# GPS_lure.net
KiCad netlist of a schematic drawn in EAGLE
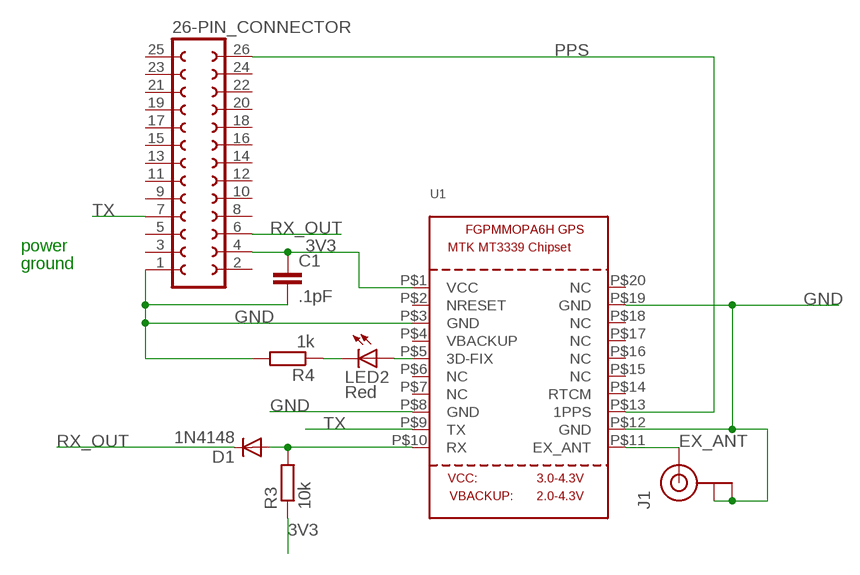
[diagram p0: schematic, sheet 1]

(export (version "E")
  (design (tool "Eeschema 10.0.6"))
  (components
    (comp (ref "26-PIN_CONNECTOR")
      (value "FE13-2W")
      (footprint "eagle-import:FE13-2W")
      (libsource (lib "eagle-import") (part "FE13-2W"))
    )
    (comp (ref "C1")
      (value ".1pF")
      (footprint "eagle-import:C0805")
      (libsource (lib "eagle-import") (part "C-EUC0805"))
    )
    (comp (ref "D1")
      (value "1N4148")
      (footprint "eagle-import:SOD123")
      (libsource (lib "eagle-import") (part "DIODE-SOD123"))
    )
    (comp (ref "J1")
      (value "U.FL")
      (footprint "eagle-import:U.FL")
      (libsource (lib "eagle-import") (part "U.FL"))
    )
    (comp (ref "LED2")
      (value "Red")
      (footprint "eagle-import:CHIPLED_1206")
      (libsource (lib "eagle-import") (part "LEDCHIPLED_1206"))
    )
    (comp (ref "R3")
      (value "10k")
      (footprint "eagle-import:M1206")
      (libsource (lib "eagle-import") (part "R-EU_M1206"))
    )
    (comp (ref "R4")
      (value "1k")
      (footprint "eagle-import:M1206")
      (libsource (lib "eagle-import") (part "R-EU_M1206"))
    )
    (comp (ref "U1")
      (value "GPS_FGPMMOPA6H")
      (footprint "eagle-import:FGPMMOPA6H")
      (libsource (lib "eagle-import") (part "GPS_FGPMMOPA6H"))
    )
  )
  (nets
    (net (code "1") (name "/3V3") (class "Default")
      (node (ref "26-PIN_CONNECTOR") (pin "4") (pinfunction "4_4") (pintype "passive"))
      (node (ref "C1") (pin "1") (pinfunction "1_1") (pintype "passive"))
      (node (ref "R3") (pin "1") (pinfunction "1_1") (pintype "passive"))
      (node (ref "U1") (pin "P$1") (pinfunction "VCC_P$1") (pintype "bidirectional"))
    )
    (net (code "2") (name "/EX_ANT") (class "Default")
      (node (ref "J1") (pin "P$3") (pinfunction "SIGNAL_P$3") (pintype "bidirectional"))
      (node (ref "U1") (pin "P$11") (pinfunction "EX_ANT_P$11") (pintype "bidirectional"))
    )
    (net (code "3") (name "/GND") (class "Default")
      (node (ref "26-PIN_CONNECTOR") (pin "1") (pinfunction "1_1") (pintype "passive"))
      (node (ref "C1") (pin "2") (pinfunction "2_2") (pintype "passive"))
      (node (ref "J1") (pin "P$1") (pinfunction "GND_P$1") (pintype "bidirectional"))
      (node (ref "J1") (pin "P$2") (pinfunction "GND_P$2") (pintype "bidirectional"))
      (node (ref "R4") (pin "2") (pinfunction "2_2") (pintype "passive"))
      (node (ref "U1") (pin "P$12") (pinfunction "GND_P$12") (pintype "bidirectional"))
      (node (ref "U1") (pin "P$19") (pinfunction "GND_P$19") (pintype "bidirectional"))
      (node (ref "U1") (pin "P$3") (pinfunction "GND_P$3") (pintype "bidirectional"))
      (node (ref "U1") (pin "P$8") (pinfunction "GND_P$8") (pintype "bidirectional"))
    )
    (net (code "4") (name "/PPS") (class "Default")
      (node (ref "26-PIN_CONNECTOR") (pin "26") (pinfunction "26_26") (pintype "passive"))
      (node (ref "U1") (pin "P$13") (pinfunction "1PPS_P$13") (pintype "bidirectional"))
    )
    (net (code "5") (name "/RX_OUT") (class "Default")
      (node (ref "26-PIN_CONNECTOR") (pin "6") (pinfunction "6_6") (pintype "passive"))
      (node (ref "D1") (pin "C") (pinfunction "C_C") (pintype "passive"))
    )
    (net (code "6") (name "/TX") (class "Default")
      (node (ref "26-PIN_CONNECTOR") (pin "7") (pinfunction "7_7") (pintype "passive"))
      (node (ref "U1") (pin "P$9") (pinfunction "TX_P$9") (pintype "bidirectional"))
    )
    (net (code "7") (name "Net-(LED2-PadC)") (class "Default")
      (node (ref "LED2") (pin "C") (pinfunction "C_C") (pintype "passive"))
      (node (ref "R4") (pin "1") (pinfunction "1_1") (pintype "passive"))
    )
    (net (code "8") (name "Net-(U1-3D-FIX)") (class "Default")
      (node (ref "LED2") (pin "A") (pinfunction "A_A") (pintype "passive"))
      (node (ref "U1") (pin "P$5") (pinfunction "3D-FIX_P$5") (pintype "bidirectional"))
    )
    (net (code "9") (name "Net-(U1-RX)") (class "Default")
      (node (ref "D1") (pin "A") (pinfunction "A_A") (pintype "passive"))
      (node (ref "R3") (pin "2") (pinfunction "2_2") (pintype "passive"))
      (node (ref "U1") (pin "P$10") (pinfunction "RX_P$10") (pintype "bidirectional"))
    )
    (net (code "10") (name "unconnected-(26-PIN_CONNECTOR-Pad2)") (class "Default")
      (node (ref "26-PIN_CONNECTOR") (pin "2") (pinfunction "2_2") (pintype "passive"))
    )
    (net (code "11") (name "unconnected-(26-PIN_CONNECTOR-Pad3)") (class "Default")
      (node (ref "26-PIN_CONNECTOR") (pin "3") (pinfunction "3_3") (pintype "passive"))
    )
    (net (code "12") (name "unconnected-(26-PIN_CONNECTOR-Pad5)") (class "Default")
      (node (ref "26-PIN_CONNECTOR") (pin "5") (pinfunction "5_5") (pintype "passive"))
    )
    (net (code "13") (name "unconnected-(26-PIN_CONNECTOR-Pad8)") (class "Default")
      (node (ref "26-PIN_CONNECTOR") (pin "8") (pinfunction "8_8") (pintype "passive"))
    )
    (net (code "14") (name "unconnected-(26-PIN_CONNECTOR-Pad9)") (class "Default")
      (node (ref "26-PIN_CONNECTOR") (pin "9") (pinfunction "9_9") (pintype "passive"))
    )
    (net (code "15") (name "unconnected-(26-PIN_CONNECTOR-Pad10)") (class "Default")
      (node (ref "26-PIN_CONNECTOR") (pin "10") (pinfunction "10_10") (pintype "passive"))
    )
    (net (code "16") (name "unconnected-(26-PIN_CONNECTOR-Pad11)") (class "Default")
      (node (ref "26-PIN_CONNECTOR") (pin "11") (pinfunction "11_11") (pintype "passive"))
    )
    (net (code "17") (name "unconnected-(26-PIN_CONNECTOR-Pad12)") (class "Default")
      (node (ref "26-PIN_CONNECTOR") (pin "12") (pinfunction "12_12") (pintype "passive"))
    )
    (net (code "18") (name "unconnected-(26-PIN_CONNECTOR-Pad13)") (class "Default")
      (node (ref "26-PIN_CONNECTOR") (pin "13") (pinfunction "13_13") (pintype "passive"))
    )
    (net (code "19") (name "unconnected-(26-PIN_CONNECTOR-Pad14)") (class "Default")
      (node (ref "26-PIN_CONNECTOR") (pin "14") (pinfunction "14_14") (pintype "passive"))
    )
    (net (code "20") (name "unconnected-(26-PIN_CONNECTOR-Pad15)") (class "Default")
      (node (ref "26-PIN_CONNECTOR") (pin "15") (pinfunction "15_15") (pintype "passive"))
    )
    (net (code "21") (name "unconnected-(26-PIN_CONNECTOR-Pad16)") (class "Default")
      (node (ref "26-PIN_CONNECTOR") (pin "16") (pinfunction "16_16") (pintype "passive"))
    )
    (net (code "22") (name "unconnected-(26-PIN_CONNECTOR-Pad17)") (class "Default")
      (node (ref "26-PIN_CONNECTOR") (pin "17") (pinfunction "17_17") (pintype "passive"))
    )
    (net (code "23") (name "unconnected-(26-PIN_CONNECTOR-Pad18)") (class "Default")
      (node (ref "26-PIN_CONNECTOR") (pin "18") (pinfunction "18_18") (pintype "passive"))
    )
    (net (code "24") (name "unconnected-(26-PIN_CONNECTOR-Pad19)") (class "Default")
      (node (ref "26-PIN_CONNECTOR") (pin "19") (pinfunction "19_19") (pintype "passive"))
    )
    (net (code "25") (name "unconnected-(26-PIN_CONNECTOR-Pad20)") (class "Default")
      (node (ref "26-PIN_CONNECTOR") (pin "20") (pinfunction "20_20") (pintype "passive"))
    )
    (net (code "26") (name "unconnected-(26-PIN_CONNECTOR-Pad21)") (class "Default")
      (node (ref "26-PIN_CONNECTOR") (pin "21") (pinfunction "21_21") (pintype "passive"))
    )
    (net (code "27") (name "unconnected-(26-PIN_CONNECTOR-Pad22)") (class "Default")
      (node (ref "26-PIN_CONNECTOR") (pin "22") (pinfunction "22_22") (pintype "passive"))
    )
    (net (code "28") (name "unconnected-(26-PIN_CONNECTOR-Pad23)") (class "Default")
      (node (ref "26-PIN_CONNECTOR") (pin "23") (pinfunction "23_23") (pintype "passive"))
    )
    (net (code "29") (name "unconnected-(26-PIN_CONNECTOR-Pad24)") (class "Default")
      (node (ref "26-PIN_CONNECTOR") (pin "24") (pinfunction "24_24") (pintype "passive"))
    )
    (net (code "30") (name "unconnected-(26-PIN_CONNECTOR-Pad25)") (class "Default")
      (node (ref "26-PIN_CONNECTOR") (pin "25") (pinfunction "25_25") (pintype "passive"))
    )
    (net (code "31") (name "unconnected-(U1-NC-PadP$6)") (class "Default")
      (node (ref "U1") (pin "P$6") (pinfunction "NC_P$6") (pintype "bidirectional"))
    )
    (net (code "32") (name "unconnected-(U1-NC-PadP$7)") (class "Default")
      (node (ref "U1") (pin "P$7") (pinfunction "NC_P$7") (pintype "bidirectional"))
    )
    (net (code "33") (name "unconnected-(U1-NC-PadP$15)") (class "Default")
      (node (ref "U1") (pin "P$15") (pinfunction "NC_P$15") (pintype "bidirectional"))
    )
    (net (code "34") (name "unconnected-(U1-NC-PadP$16)") (class "Default")
      (node (ref "U1") (pin "P$16") (pinfunction "NC_P$16") (pintype "bidirectional"))
    )
    (net (code "35") (name "unconnected-(U1-NC-PadP$17)") (class "Default")
      (node (ref "U1") (pin "P$17") (pinfunction "NC_P$17") (pintype "bidirectional"))
    )
    (net (code "36") (name "unconnected-(U1-NC-PadP$18)") (class "Default")
      (node (ref "U1") (pin "P$18") (pinfunction "NC_P$18") (pintype "bidirectional"))
    )
    (net (code "37") (name "unconnected-(U1-NC-PadP$20)") (class "Default")
      (node (ref "U1") (pin "P$20") (pinfunction "NC_P$20") (pintype "bidirectional"))
    )
    (net (code "38") (name "unconnected-(U1-NRESET-PadP$2)") (class "Default")
      (node (ref "U1") (pin "P$2") (pinfunction "NRESET_P$2") (pintype "bidirectional"))
    )
    (net (code "39") (name "unconnected-(U1-RTCM-PadP$14)") (class "Default")
      (node (ref "U1") (pin "P$14") (pinfunction "RTCM_P$14") (pintype "bidirectional"))
    )
    (net (code "40") (name "unconnected-(U1-VBACKUP-PadP$4)") (class "Default")
      (node (ref "U1") (pin "P$4") (pinfunction "VBACKUP_P$4") (pintype "bidirectional"))
    )
  )
)
